# Peripherals.net
KiCad netlist of a schematic drawn in Altium Designer
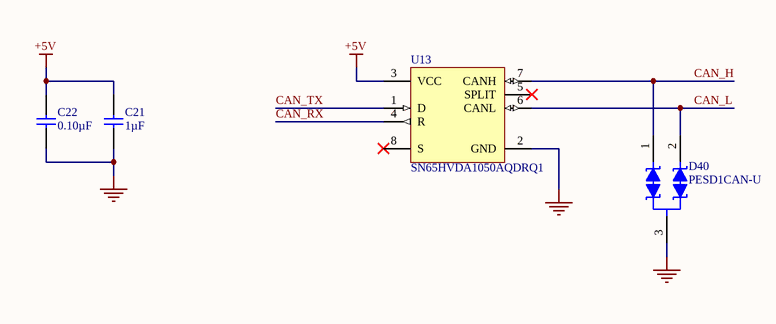
[diagram p0: Peripherals.SchDoc]

(export (version "E")
  (design (tool "Eeschema 10.0.6"))
  (components
    (comp (ref "C21")
      (value "1µF")
      (footprint "CAP-0805-M")
      (fields
        (field (name "PART NUMBER") "CC0805KKX7R7BB105")
        (field (name "TOLERANCE") "±10%")
        (field (name "VOLTAGE") "16V")
      )
      (libsource (lib "Capacitors") (part "Capacitor"))
    )
    (comp (ref "C22")
      (value "0.10µF")
      (footprint "CAP-0402-M")
      (fields
        (field (name "PART NUMBER") "CC0402KRX7R7BB104")
        (field (name "TOLERANCE") "±10%")
        (field (name "VOLTAGE") "16V")
      )
      (libsource (lib "Capacitors") (part "Capacitor"))
    )
    (comp (ref "D40")
      (value "PESD1CAN-U")
      (footprint "SOT65P210X110-3N")
      (libsource (lib "PDU-UV17") (part "PESD1CAN-U"))
    )
    (comp (ref "U13")
      (value "SN65HVDA1050AQDRQ1")
      (footprint "SOIC127P600X175-8M")
      (description "CAN transceiver")
      (libsource (lib "PDU-UV17") (part "SN65HVDA1050AQDRQ1"))
    )
  )
  (nets
    (net (code "1") (name "+5V") (class "Default")
      (node (ref "C21") (pin "1") (pinfunction "1_1") (pintype "passive"))
      (node (ref "C22") (pin "2") (pinfunction "2_2") (pintype "passive"))
      (node (ref "U13") (pin "3") (pinfunction "VCC_3") (pintype "power_in"))
    )
    (net (code "2") (name "/CAN_H") (class "Default")
      (node (ref "D40") (pin "1") (pinfunction "1_1") (pintype "passive"))
      (node (ref "U13") (pin "7") (pinfunction "CANH_7") (pintype "bidirectional"))
    )
    (net (code "3") (name "/CAN_L") (class "Default")
      (node (ref "D40") (pin "2") (pinfunction "2_2") (pintype "passive"))
      (node (ref "U13") (pin "6") (pinfunction "CANL_6") (pintype "bidirectional"))
    )
    (net (code "4") (name "/CAN_RX") (class "Default")
      (node (ref "U13") (pin "4") (pinfunction "R_4") (pintype "output"))
    )
    (net (code "5") (name "/CAN_TX") (class "Default")
      (node (ref "U13") (pin "1") (pinfunction "D_1") (pintype "input"))
    )
    (net (code "6") (name "GND") (class "Default")
      (node (ref "C21") (pin "2") (pinfunction "2_2") (pintype "passive"))
      (node (ref "C22") (pin "1") (pinfunction "1_1") (pintype "passive"))
      (node (ref "D40") (pin "3") (pinfunction "3_3") (pintype "passive"))
      (node (ref "U13") (pin "2") (pinfunction "GND_2") (pintype "power_in"))
    )
    (net (code "7") (name "unconnected-(U13-S-Pad8)") (class "Default")
      (node (ref "U13") (pin "8") (pinfunction "S_8") (pintype "passive+no_connect"))
    )
    (net (code "8") (name "unconnected-(U13-SPLIT-Pad5)") (class "Default")
      (node (ref "U13") (pin "5") (pinfunction "SPLIT_5") (pintype "passive+no_connect"))
    )
  )
)
